# me433_1.net
KiCad netlist of a schematic drawn in EAGLE
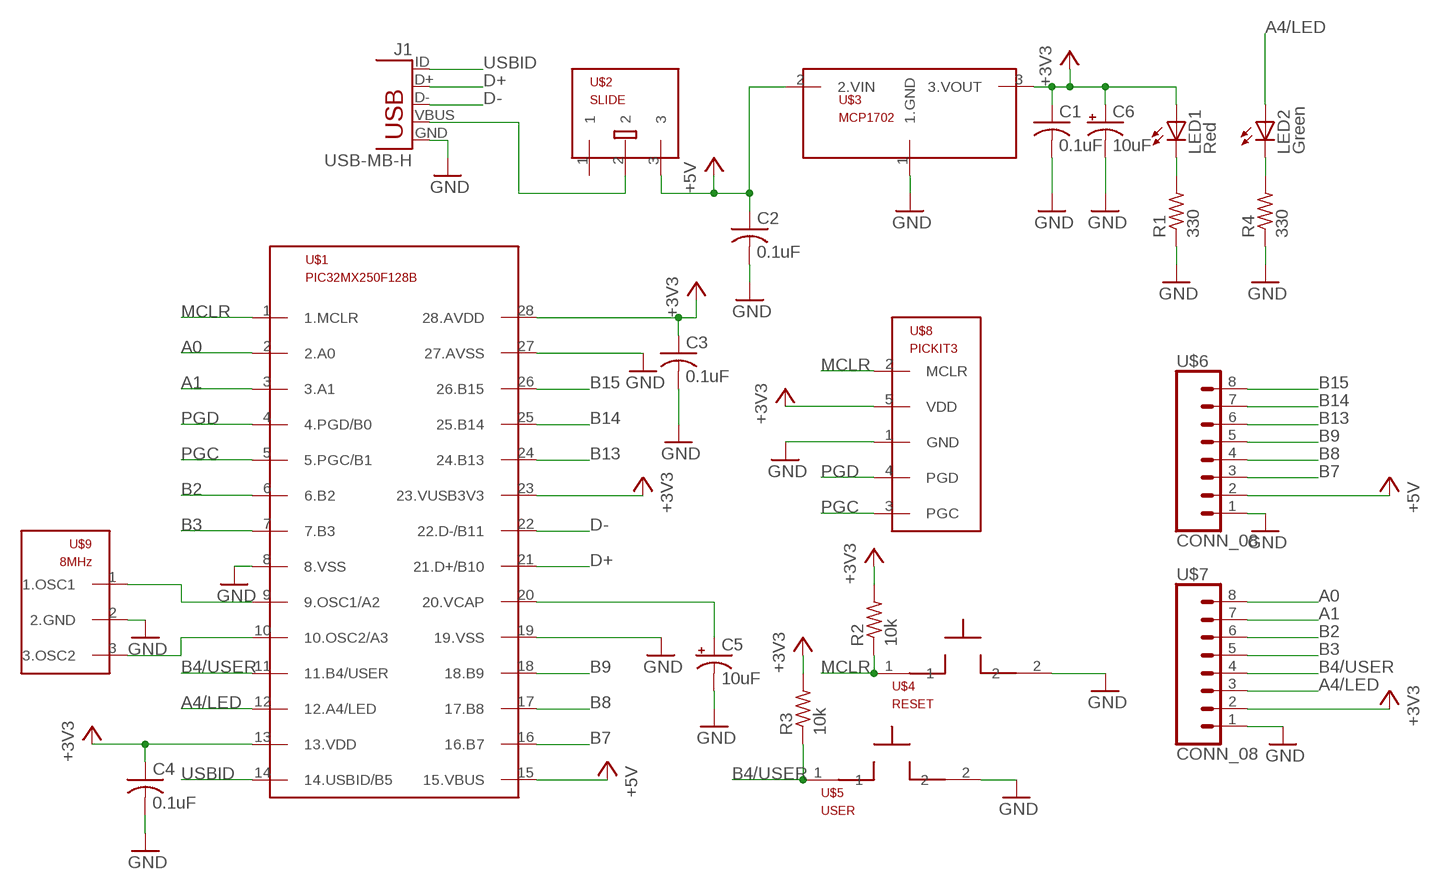
[diagram p0: schematic, sheet 1]

(export (version "E")
  (design (tool "Eeschema 10.0.6"))
  (components
    (comp (ref "C1")
      (value "0.1uF")
      (footprint "eagle-import:C025-025X050")
      (libsource (lib "eagle-import") (part "C-US025-025X050"))
    )
    (comp (ref "C2")
      (value "0.1uF")
      (footprint "eagle-import:C025-025X050")
      (libsource (lib "eagle-import") (part "C-US025-025X050"))
    )
    (comp (ref "C3")
      (value "0.1uF")
      (footprint "eagle-import:C025-025X050")
      (libsource (lib "eagle-import") (part "C-US025-025X050"))
    )
    (comp (ref "C4")
      (value "0.1uF")
      (footprint "eagle-import:C025-025X050")
      (libsource (lib "eagle-import") (part "C-US025-025X050"))
    )
    (comp (ref "C5")
      (value "10uF")
      (footprint "eagle-import:B45181B")
      (libsource (lib "eagle-import") (part "CPOL-USB45181B"))
    )
    (comp (ref "C6")
      (value "10uF")
      (footprint "eagle-import:B45181B")
      (libsource (lib "eagle-import") (part "CPOL-USB45181B"))
    )
    (comp (ref "J1")
      (value "USB-MB-H")
      (footprint "eagle-import:USB-MB-H")
      (libsource (lib "eagle-import") (part "USB-MB-H"))
    )
    (comp (ref "LED1")
      (value "Red")
      (footprint "eagle-import:LED3MM")
      (libsource (lib "eagle-import") (part "LED3MM"))
    )
    (comp (ref "LED2")
      (value "Green")
      (footprint "eagle-import:LED3MM")
      (libsource (lib "eagle-import") (part "LED3MM"))
    )
    (comp (ref "R1")
      (value "330")
      (footprint "eagle-import:0207_10")
      (libsource (lib "eagle-import") (part "R-US_0207/10"))
    )
    (comp (ref "R2")
      (value "10k")
      (footprint "eagle-import:0207_10")
      (libsource (lib "eagle-import") (part "R-US_0207/10"))
    )
    (comp (ref "R3")
      (value "10k")
      (footprint "eagle-import:0207_10")
      (libsource (lib "eagle-import") (part "R-US_0207/10"))
    )
    (comp (ref "R4")
      (value "330")
      (footprint "eagle-import:0207_10")
      (libsource (lib "eagle-import") (part "R-US_0207/10"))
    )
    (comp (ref "U$1")
      (value "PIC32MX250F128B")
      (footprint "eagle-import:DIL28-3")
      (libsource (lib "eagle-import") (part "PIC32MX250F128B"))
    )
    (comp (ref "U$2")
      (value "SLIDE")
      (footprint "eagle-import:SLIDE")
      (libsource (lib "eagle-import") (part "SLIDE"))
    )
    (comp (ref "U$3")
      (value "MCP1702")
      (footprint "eagle-import:TO92")
      (libsource (lib "eagle-import") (part "MCP1702"))
    )
    (comp (ref "U$4")
      (value "RESET")
      (footprint "eagle-import:PB")
      (libsource (lib "eagle-import") (part "PB"))
    )
    (comp (ref "U$5")
      (value "USER")
      (footprint "eagle-import:PB")
      (libsource (lib "eagle-import") (part "PB"))
    )
    (comp (ref "U$6")
      (value "CONN_08")
      (footprint "eagle-import:1X08")
      (libsource (lib "eagle-import") (part "CONN_08"))
    )
    (comp (ref "U$7")
      (value "CONN_08")
      (footprint "eagle-import:1X08")
      (libsource (lib "eagle-import") (part "CONN_08"))
    )
    (comp (ref "U$8")
      (value "PICKIT3")
      (footprint "eagle-import:1X05")
      (libsource (lib "eagle-import") (part "PICKIT3"))
    )
    (comp (ref "U$9")
      (value "8MHz")
      (footprint "eagle-import:OSC")
      (libsource (lib "eagle-import") (part "OSC"))
    )
  )
  (nets
    (net (code "1") (name "+3V3") (class "Default")
      (node (ref "C1") (pin "1") (pinfunction "1_1") (pintype "passive"))
      (node (ref "C3") (pin "1") (pinfunction "1_1") (pintype "passive"))
      (node (ref "C4") (pin "1") (pinfunction "1_1") (pintype "passive"))
      (node (ref "C6") (pin "+") (pinfunction "+_+") (pintype "passive"))
      (node (ref "LED1") (pin "A") (pinfunction "A_A") (pintype "passive"))
      (node (ref "R2") (pin "2") (pinfunction "2_2") (pintype "passive"))
      (node (ref "R3") (pin "2") (pinfunction "2_2") (pintype "passive"))
      (node (ref "U$1") (pin "13") (pinfunction "13.VDD_13") (pintype "bidirectional"))
      (node (ref "U$1") (pin "23") (pinfunction "23.VUSB3V3_23") (pintype "bidirectional"))
      (node (ref "U$1") (pin "28") (pinfunction "28.AVDD_28") (pintype "bidirectional"))
      (node (ref "U$3") (pin "3") (pinfunction "3.VOUT_3") (pintype "bidirectional"))
      (node (ref "U$7") (pin "2") (pinfunction "2_2") (pintype "passive"))
      (node (ref "U$8") (pin "5") (pinfunction "VDD_5") (pintype "bidirectional"))
    )
    (net (code "2") (name "+5V") (class "Default")
      (node (ref "C2") (pin "1") (pinfunction "1_1") (pintype "passive"))
      (node (ref "U$1") (pin "15") (pinfunction "15.VBUS_15") (pintype "bidirectional"))
      (node (ref "U$2") (pin "3") (pinfunction "3_3") (pintype "bidirectional"))
      (node (ref "U$3") (pin "2") (pinfunction "2.VIN_2") (pintype "bidirectional"))
      (node (ref "U$6") (pin "2") (pinfunction "2_2") (pintype "passive"))
    )
    (net (code "3") (name "/A0") (class "Default")
      (node (ref "U$1") (pin "2") (pinfunction "2.A0_2") (pintype "bidirectional"))
      (node (ref "U$7") (pin "8") (pinfunction "8_8") (pintype "passive"))
    )
    (net (code "4") (name "/A1") (class "Default")
      (node (ref "U$1") (pin "3") (pinfunction "3.A1_3") (pintype "bidirectional"))
      (node (ref "U$7") (pin "7") (pinfunction "7_7") (pintype "passive"))
    )
    (net (code "5") (name "/A4{slash}LED") (class "Default")
      (node (ref "LED2") (pin "A") (pinfunction "A_A") (pintype "passive"))
      (node (ref "U$1") (pin "12") (pinfunction "12.A4/LED_12") (pintype "bidirectional"))
      (node (ref "U$7") (pin "3") (pinfunction "3_3") (pintype "passive"))
    )
    (net (code "6") (name "/B2") (class "Default")
      (node (ref "U$1") (pin "6") (pinfunction "6.B2_6") (pintype "bidirectional"))
      (node (ref "U$7") (pin "6") (pinfunction "6_6") (pintype "passive"))
    )
    (net (code "7") (name "/B3") (class "Default")
      (node (ref "U$1") (pin "7") (pinfunction "7.B3_7") (pintype "bidirectional"))
      (node (ref "U$7") (pin "5") (pinfunction "5_5") (pintype "passive"))
    )
    (net (code "8") (name "/B4{slash}USER") (class "Default")
      (node (ref "R3") (pin "1") (pinfunction "1_1") (pintype "passive"))
      (node (ref "U$1") (pin "11") (pinfunction "11.B4/USER_11") (pintype "bidirectional"))
      (node (ref "U$5") (pin "1") (pinfunction "1_1") (pintype "bidirectional"))
      (node (ref "U$7") (pin "4") (pinfunction "4_4") (pintype "passive"))
    )
    (net (code "9") (name "/B7") (class "Default")
      (node (ref "U$1") (pin "16") (pinfunction "16.B7_16") (pintype "bidirectional"))
      (node (ref "U$6") (pin "3") (pinfunction "3_3") (pintype "passive"))
    )
    (net (code "10") (name "/B8") (class "Default")
      (node (ref "U$1") (pin "17") (pinfunction "17.B8_17") (pintype "bidirectional"))
      (node (ref "U$6") (pin "4") (pinfunction "4_4") (pintype "passive"))
    )
    (net (code "11") (name "/B9") (class "Default")
      (node (ref "U$1") (pin "18") (pinfunction "18.B9_18") (pintype "bidirectional"))
      (node (ref "U$6") (pin "5") (pinfunction "5_5") (pintype "passive"))
    )
    (net (code "12") (name "/B13") (class "Default")
      (node (ref "U$1") (pin "24") (pinfunction "24.B13_24") (pintype "bidirectional"))
      (node (ref "U$6") (pin "6") (pinfunction "6_6") (pintype "passive"))
    )
    (net (code "13") (name "/B14") (class "Default")
      (node (ref "U$1") (pin "25") (pinfunction "25.B14_25") (pintype "bidirectional"))
      (node (ref "U$6") (pin "7") (pinfunction "7_7") (pintype "passive"))
    )
    (net (code "14") (name "/B15") (class "Default")
      (node (ref "U$1") (pin "26") (pinfunction "26.B15_26") (pintype "bidirectional"))
      (node (ref "U$6") (pin "8") (pinfunction "8_8") (pintype "passive"))
    )
    (net (code "15") (name "/D+") (class "Default")
      (node (ref "J1") (pin "D+") (pinfunction "D+_D+") (pintype "bidirectional"))
      (node (ref "U$1") (pin "21") (pinfunction "21.D+/B10_21") (pintype "bidirectional"))
    )
    (net (code "16") (name "/D-") (class "Default")
      (node (ref "J1") (pin "D-") (pinfunction "D-_D-") (pintype "bidirectional"))
      (node (ref "U$1") (pin "22") (pinfunction "22.D-/B11_22") (pintype "bidirectional"))
    )
    (net (code "17") (name "/MCLR") (class "Default")
      (node (ref "R2") (pin "1") (pinfunction "1_1") (pintype "passive"))
      (node (ref "U$1") (pin "1") (pinfunction "1.MCLR_1") (pintype "bidirectional"))
      (node (ref "U$4") (pin "1") (pinfunction "1_1") (pintype "bidirectional"))
      (node (ref "U$8") (pin "2") (pinfunction "MCLR_2") (pintype "bidirectional"))
    )
    (net (code "18") (name "/PGC") (class "Default")
      (node (ref "U$1") (pin "5") (pinfunction "5.PGC/B1_5") (pintype "bidirectional"))
      (node (ref "U$8") (pin "3") (pinfunction "PGC_3") (pintype "bidirectional"))
    )
    (net (code "19") (name "/PGD") (class "Default")
      (node (ref "U$1") (pin "4") (pinfunction "4.PGD/B0_4") (pintype "bidirectional"))
      (node (ref "U$8") (pin "4") (pinfunction "PGD_4") (pintype "bidirectional"))
    )
    (net (code "20") (name "/USBID") (class "Default")
      (node (ref "J1") (pin "ID") (pinfunction "ID_ID") (pintype "bidirectional"))
      (node (ref "U$1") (pin "14") (pinfunction "14.USBID/B5_14") (pintype "bidirectional"))
    )
    (net (code "21") (name "GND") (class "Default")
      (node (ref "C1") (pin "2") (pinfunction "2_2") (pintype "passive"))
      (node (ref "C2") (pin "2") (pinfunction "2_2") (pintype "passive"))
      (node (ref "C3") (pin "2") (pinfunction "2_2") (pintype "passive"))
      (node (ref "C4") (pin "2") (pinfunction "2_2") (pintype "passive"))
      (node (ref "C5") (pin "-") (pinfunction "-_-") (pintype "passive"))
      (node (ref "C6") (pin "-") (pinfunction "-_-") (pintype "passive"))
      (node (ref "J1") (pin "GND") (pinfunction "GND_GND") (pintype "bidirectional"))
      (node (ref "R1") (pin "1") (pinfunction "1_1") (pintype "passive"))
      (node (ref "R4") (pin "1") (pinfunction "1_1") (pintype "passive"))
      (node (ref "U$1") (pin "19") (pinfunction "19.VSS_19") (pintype "bidirectional"))
      (node (ref "U$1") (pin "27") (pinfunction "27.AVSS_27") (pintype "bidirectional"))
      (node (ref "U$1") (pin "8") (pinfunction "8.VSS_8") (pintype "bidirectional"))
      (node (ref "U$3") (pin "1") (pinfunction "1.GND_1") (pintype "bidirectional"))
      (node (ref "U$4") (pin "2") (pinfunction "2_2") (pintype "bidirectional"))
      (node (ref "U$5") (pin "2") (pinfunction "2_2") (pintype "bidirectional"))
      (node (ref "U$6") (pin "1") (pinfunction "1_1") (pintype "passive"))
      (node (ref "U$7") (pin "1") (pinfunction "1_1") (pintype "passive"))
      (node (ref "U$8") (pin "1") (pinfunction "GND_1") (pintype "bidirectional"))
      (node (ref "U$9") (pin "2") (pinfunction "2.GND_2") (pintype "bidirectional"))
    )
    (net (code "22") (name "Net-(J1-PadVBUS)") (class "Default")
      (node (ref "J1") (pin "VBUS") (pinfunction "VBUS_VBUS") (pintype "bidirectional"))
      (node (ref "U$2") (pin "2") (pinfunction "2_2") (pintype "bidirectional"))
    )
    (net (code "23") (name "Net-(LED1-C)") (class "Default")
      (node (ref "LED1") (pin "K") (pinfunction "C_K") (pintype "passive"))
      (node (ref "R1") (pin "2") (pinfunction "2_2") (pintype "passive"))
    )
    (net (code "24") (name "Net-(LED2-C)") (class "Default")
      (node (ref "LED2") (pin "K") (pinfunction "C_K") (pintype "passive"))
      (node (ref "R4") (pin "2") (pinfunction "2_2") (pintype "passive"))
    )
    (net (code "25") (name "Net-(U$1-9.OSC1{slash}A2)") (class "Default")
      (node (ref "U$1") (pin "9") (pinfunction "9.OSC1/A2_9") (pintype "bidirectional"))
      (node (ref "U$9") (pin "1") (pinfunction "1.OSC1_1") (pintype "bidirectional"))
    )
    (net (code "26") (name "Net-(U$1-10.OSC2{slash}A3)") (class "Default")
      (node (ref "U$1") (pin "10") (pinfunction "10.OSC2/A3_10") (pintype "bidirectional"))
      (node (ref "U$9") (pin "3") (pinfunction "3.OSC2_3") (pintype "bidirectional"))
    )
    (net (code "27") (name "Net-(U$1-20.VCAP)") (class "Default")
      (node (ref "C5") (pin "+") (pinfunction "+_+") (pintype "passive"))
      (node (ref "U$1") (pin "20") (pinfunction "20.VCAP_20") (pintype "bidirectional"))
    )
    (net (code "28") (name "unconnected-(U$2-Pad1)") (class "Default")
      (node (ref "U$2") (pin "1") (pinfunction "1_1") (pintype "bidirectional"))
    )
  )
)
